# RPI_3.net
KiCad netlist of a schematic drawn in Altium Designer
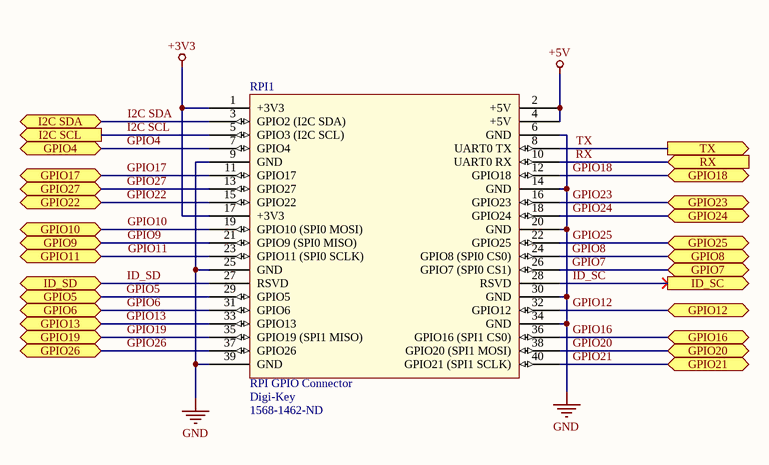
[diagram p0: RPI 3.SchDoc]

(export (version "E")
  (design (tool "Eeschema 10.0.6"))
  (components
    (comp (ref "RPI1")
      (value "RPI GPIO Connector")
      (footprint "rpi")
      (description "GPIO Header for Raspberry Pi A+/B+/Pi 2/Pi 3 - 2x20")
      (fields
        (field (name "MANUFACTURER") "SparkFun Electronics")
        (field (name "MANUFACTURER PART NUMBER") "PRT-14017")
        (field (name "SUPPLIER 1") "Digi-Key")
        (field (name "SUPPLIER PART NUMBER 1") "1568-1462-ND")
      )
      (libsource (lib "rpi") (part "rpi connector"))
    )
  )
  (nets
    (net (code "1") (name "+3V3") (class "Default")
      (node (ref "RPI1") (pin "1") (pinfunction "+3V3_1") (pintype "power_in"))
      (node (ref "RPI1") (pin "17") (pinfunction "+3V3_17") (pintype "power_in"))
    )
    (net (code "2") (name "+5V") (class "Default")
      (node (ref "RPI1") (pin "2") (pinfunction "+5V_2") (pintype "power_in"))
      (node (ref "RPI1") (pin "4") (pinfunction "+5V_4") (pintype "power_in"))
    )
    (net (code "3") (name "/GPIO4") (class "Default")
      (node (ref "RPI1") (pin "7") (pinfunction "GPIO4_7") (pintype "bidirectional"))
    )
    (net (code "4") (name "/GPIO5") (class "Default")
      (node (ref "RPI1") (pin "29") (pinfunction "GPIO5_29") (pintype "bidirectional"))
    )
    (net (code "5") (name "/GPIO6") (class "Default")
      (node (ref "RPI1") (pin "31") (pinfunction "GPIO6_31") (pintype "bidirectional"))
    )
    (net (code "6") (name "/GPIO7") (class "Default")
      (node (ref "RPI1") (pin "26") (pinfunction "GPIO7_(SPI0_CS1)_26") (pintype "bidirectional"))
    )
    (net (code "7") (name "/GPIO8") (class "Default")
      (node (ref "RPI1") (pin "24") (pinfunction "GPIO8_(SPI0_CS0)_24") (pintype "bidirectional"))
    )
    (net (code "8") (name "/GPIO9") (class "Default")
      (node (ref "RPI1") (pin "21") (pinfunction "GPIO9_(SPI0_MISO)_21") (pintype "bidirectional"))
    )
    (net (code "9") (name "/GPIO10") (class "Default")
      (node (ref "RPI1") (pin "19") (pinfunction "GPIO10_(SPI0_MOSI)_19") (pintype "bidirectional"))
    )
    (net (code "10") (name "/GPIO11") (class "Default")
      (node (ref "RPI1") (pin "23") (pinfunction "GPIO11_(SPI0_SCLK)_23") (pintype "bidirectional"))
    )
    (net (code "11") (name "/GPIO12") (class "Default")
      (node (ref "RPI1") (pin "32") (pinfunction "GPIO12_32") (pintype "bidirectional"))
    )
    (net (code "12") (name "/GPIO13") (class "Default")
      (node (ref "RPI1") (pin "33") (pinfunction "GPIO13_33") (pintype "bidirectional"))
    )
    (net (code "13") (name "/GPIO16") (class "Default")
      (node (ref "RPI1") (pin "36") (pinfunction "GPIO16_(SPI1_CS0)_36") (pintype "bidirectional"))
    )
    (net (code "14") (name "/GPIO17") (class "Default")
      (node (ref "RPI1") (pin "11") (pinfunction "GPIO17_11") (pintype "bidirectional"))
    )
    (net (code "15") (name "/GPIO18") (class "Default")
      (node (ref "RPI1") (pin "12") (pinfunction "GPIO18_12") (pintype "bidirectional"))
    )
    (net (code "16") (name "/GPIO19") (class "Default")
      (node (ref "RPI1") (pin "35") (pinfunction "GPIO19_(SPI1_MISO)_35") (pintype "bidirectional"))
    )
    (net (code "17") (name "/GPIO20") (class "Default")
      (node (ref "RPI1") (pin "38") (pinfunction "GPIO20_(SPI1_MOSI)_38") (pintype "bidirectional"))
    )
    (net (code "18") (name "/GPIO21") (class "Default")
      (node (ref "RPI1") (pin "40") (pinfunction "GPIO21_(SPI1_SCLK)_40") (pintype "bidirectional"))
    )
    (net (code "19") (name "/GPIO22") (class "Default")
      (node (ref "RPI1") (pin "15") (pinfunction "GPIO22_15") (pintype "bidirectional"))
    )
    (net (code "20") (name "/GPIO23") (class "Default")
      (node (ref "RPI1") (pin "16") (pinfunction "GPIO23_16") (pintype "bidirectional"))
    )
    (net (code "21") (name "/GPIO24") (class "Default")
      (node (ref "RPI1") (pin "18") (pinfunction "GPIO24_18") (pintype "bidirectional"))
    )
    (net (code "22") (name "/GPIO25") (class "Default")
      (node (ref "RPI1") (pin "22") (pinfunction "GPIO25_22") (pintype "bidirectional"))
    )
    (net (code "23") (name "/GPIO26") (class "Default")
      (node (ref "RPI1") (pin "37") (pinfunction "GPIO26_37") (pintype "bidirectional"))
    )
    (net (code "24") (name "/GPIO27") (class "Default")
      (node (ref "RPI1") (pin "13") (pinfunction "GPIO27_13") (pintype "bidirectional"))
    )
    (net (code "25") (name "/I2C SCL") (class "Default")
      (node (ref "RPI1") (pin "5") (pinfunction "GPIO3_(I2C_SCL)_5") (pintype "bidirectional"))
    )
    (net (code "26") (name "/I2C SDA") (class "Default")
      (node (ref "RPI1") (pin "3") (pinfunction "GPIO2_(I2C_SDA)_3") (pintype "bidirectional"))
    )
    (net (code "27") (name "/ID_SC") (class "Default")
      (node (ref "RPI1") (pin "28") (pinfunction "RSVD_28") (pintype "passive+no_connect"))
    )
    (net (code "28") (name "/ID_SD") (class "Default")
      (node (ref "RPI1") (pin "27") (pinfunction "RSVD_27") (pintype "passive"))
    )
    (net (code "29") (name "/RX") (class "Default")
      (node (ref "RPI1") (pin "10") (pinfunction "UART0_RX_10") (pintype "bidirectional"))
    )
    (net (code "30") (name "/TX") (class "Default")
      (node (ref "RPI1") (pin "8") (pinfunction "UART0_TX_8") (pintype "bidirectional"))
    )
    (net (code "31") (name "GND") (class "Default")
      (node (ref "RPI1") (pin "14") (pinfunction "GND_14") (pintype "power_in"))
      (node (ref "RPI1") (pin "20") (pinfunction "GND_20") (pintype "power_in"))
      (node (ref "RPI1") (pin "25") (pinfunction "GND_25") (pintype "power_in"))
      (node (ref "RPI1") (pin "30") (pinfunction "GND_30") (pintype "power_in"))
      (node (ref "RPI1") (pin "34") (pinfunction "GND_34") (pintype "passive"))
      (node (ref "RPI1") (pin "39") (pinfunction "GND_39") (pintype "power_in"))
      (node (ref "RPI1") (pin "6") (pinfunction "GND_6") (pintype "power_in"))
      (node (ref "RPI1") (pin "9") (pinfunction "GND_9") (pintype "power_in"))
    )
  )
)
